# ProPrj_RS485_to_TTL_Converter_2026-02-25.net
KiCad netlist of a schematic drawn in EasyEDA Pro
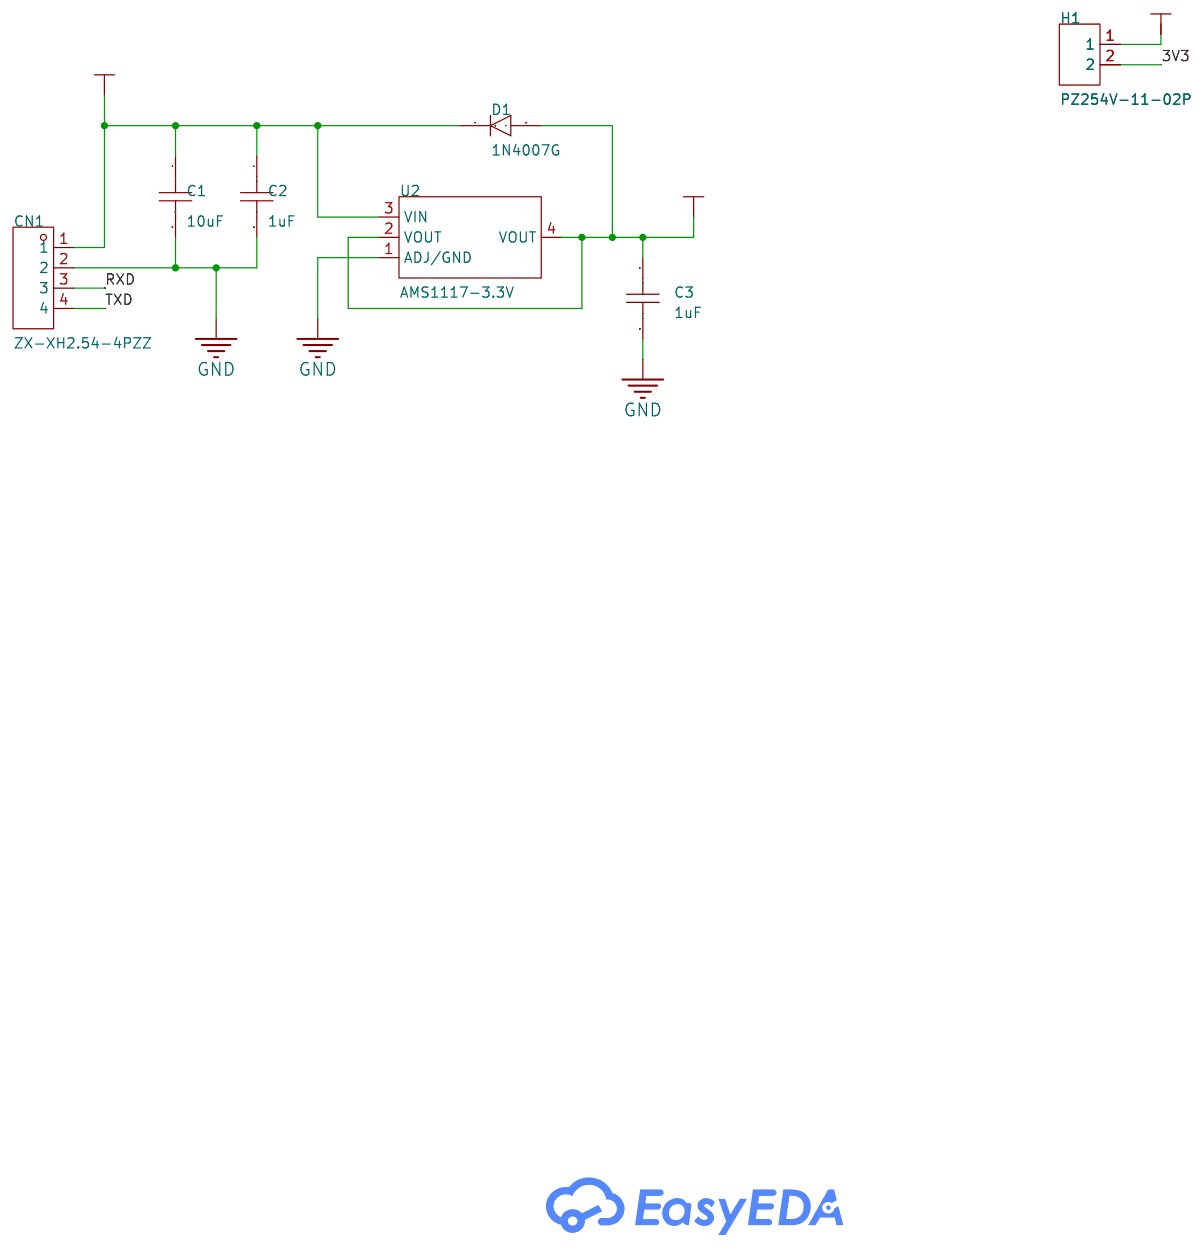
[diagram p0: Power Supply]
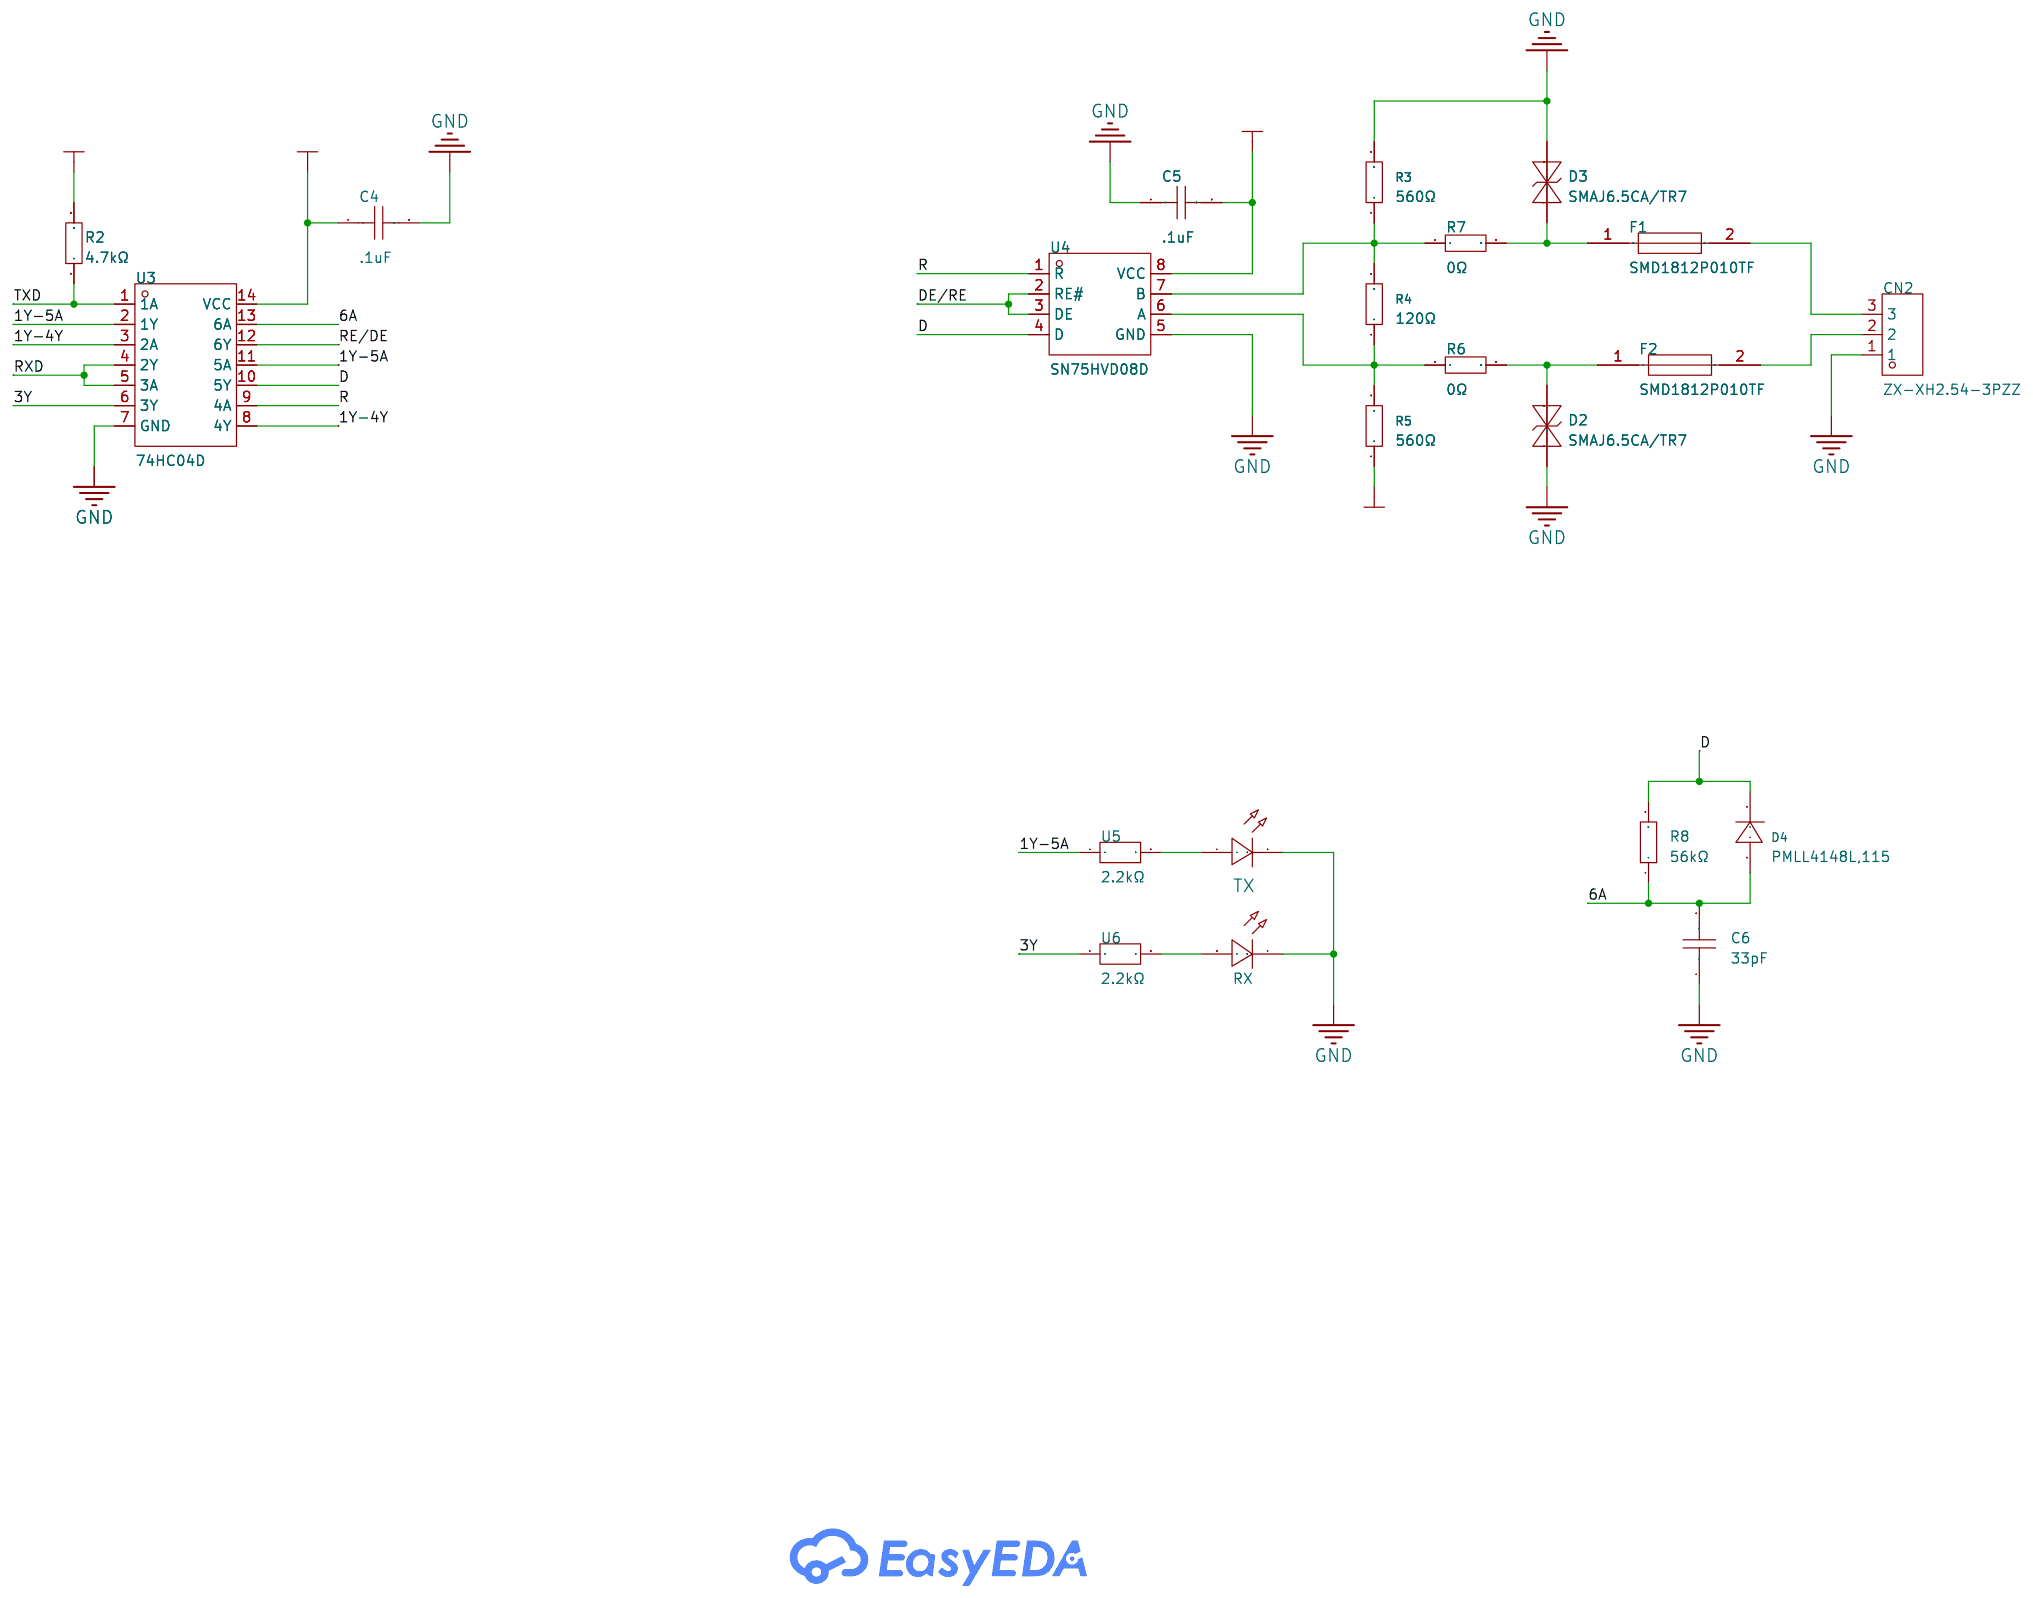
[diagram p1: RS485]

(export (version "E")
  (design (tool "Eeschema 10.0.6"))
  (components
    (comp (ref "C1")
      (value "10uF")
      (footprint "easyedapro:C0603")
      (libsource (lib "easyedapro") (part "CAP"))
    )
    (comp (ref "C2") (value "1uF") (footprint "easyedapro:C0603") (libsource (lib "easyedapro") (part "CAP")))
    (comp (ref "C3") (value "1uF") (footprint "easyedapro:C0603") (libsource (lib "easyedapro") (part "CAP")))
    (comp (ref "CN1")
      (value "ZX-XH2.54-4PZZ")
      (footprint "easyedapro:CONN-TH_4P-P2.50_4PIN")
      (fields (field (name "Manufacturer") "Megastar(兆星)"))
      (libsource (lib "easyedapro") (part "ZX-XH2.54-4PZZ"))
    )
    (comp (ref "D1")
      (value "1N4007G")
      (footprint "easyedapro:SMA_L4.4-W2.6-LS5.0-RD")
      (fields (field (name "Manufacturer") "SHIKUES(时科)"))
      (libsource (lib "easyedapro") (part "1N4007G"))
    )
    (comp (ref "H1")
      (value "PZ254V-11-02P")
      (footprint "easyedapro:HDR-TH_2P-P2.54-V-M")
      (fields (field (name "Manufacturer") "XFCN(兴飞)"))
      (libsource (lib "easyedapro") (part "PZ254V-11-02P"))
    )
    (comp (ref "U2")
      (value "AMS1117-3.3V")
      (footprint "easyedapro:SOT-223-4_L6.5-W3.5-P2.30-LS7.0-BR")
      (fields (field (name "Manufacturer") "WPMtek(维攀)"))
      (libsource (lib "easyedapro") (part "AMS1117-3.3V"))
    )
    (comp (ref "C4")
      (value ".1uF")
      (footprint "easyedapro:C0603")
      (libsource (lib "easyedapro") (part "CAP"))
    )
    (comp (ref "C5")
      (value ".1uF")
      (footprint "easyedapro:C0603")
      (libsource (lib "easyedapro") (part "CAP"))
    )
    (comp (ref "C6")
      (value "33pF")
      (footprint "easyedapro:C0603")
      (libsource (lib "easyedapro") (part "CAP"))
    )
    (comp (ref "CN2")
      (value "ZX-XH2.54-3PZZ")
      (footprint "easyedapro:CONN-TH_3P-P2.54_2501S-3P")
      (fields (field (name "Manufacturer") "Megastar(兆星)"))
      (libsource (lib "easyedapro") (part "ZX-XH2.54-3PZZ"))
    )
    (comp (ref "D2")
      (value "SMAJ6.5CA/TR7")
      (footprint "easyedapro:SMA_L4.3-W2.6-LS5.1-BI")
      (fields (field (name "Manufacturer") "Brightking(君耀电子)"))
      (libsource (lib "easyedapro") (part "SMAJ6.5CA/TR7"))
    )
    (comp (ref "D3")
      (value "SMAJ6.5CA/TR7")
      (footprint "easyedapro:SMA_L4.3-W2.6-LS5.1-BI")
      (fields (field (name "Manufacturer") "Brightking(君耀电子)"))
      (libsource (lib "easyedapro") (part "SMAJ6.5CA/TR7"))
    )
    (comp (ref "D4")
      (value "PMLL4148L,115")
      (footprint "easyedapro:SOD-80_L3.5-W1.5-RD")
      (fields (field (name "Manufacturer") "Nexperia(安世)"))
      (libsource (lib "easyedapro") (part "PMLL4148L,115"))
    )
    (comp (ref "F1")
      (value "SMD1812P010TF")
      (footprint "easyedapro:F1812")
      (fields (field (name "Manufacturer") "PTTC(聚鼎)"))
      (libsource (lib "easyedapro") (part "SMD1812P010TF_C495355"))
    )
    (comp (ref "F2")
      (value "SMD1812P010TF")
      (footprint "easyedapro:F1812")
      (fields (field (name "Manufacturer") "PTTC(聚鼎)"))
      (libsource (lib "easyedapro") (part "SMD1812P010TF_C495355"))
    )
    (comp (ref "R2")
      (value "4.7kΩ")
      (footprint "easyedapro:R0805")
      (fields
        (field (name "Manufacturer Part") "0805W8F4701T5E")
        (field (name "Manufacturer") "UNI-ROYAL(厚声)")
      )
      (libsource (lib "easyedapro") (part "0805W8F4701T5E"))
    )
    (comp (ref "R3")
      (value "560Ω")
      (footprint "easyedapro:R0805")
      (fields
        (field (name "Manufacturer Part") "0805W8F5600T5E")
        (field (name "Manufacturer") "UNI-ROYAL(厚声)")
      )
      (libsource (lib "easyedapro") (part "0805W8F5600T5E"))
    )
    (comp (ref "R4")
      (value "120Ω")
      (footprint "easyedapro:R0805")
      (fields
        (field (name "Manufacturer Part") "0805W8F1200T5E")
        (field (name "Manufacturer") "UNI-ROYAL(厚声)")
      )
      (libsource (lib "easyedapro") (part "0805W8F1200T5E"))
    )
    (comp (ref "R5")
      (value "560Ω")
      (footprint "easyedapro:R0805")
      (fields
        (field (name "Manufacturer Part") "0805W8F5600T5E")
        (field (name "Manufacturer") "UNI-ROYAL(厚声)")
      )
      (libsource (lib "easyedapro") (part "0805W8F5600T5E"))
    )
    (comp (ref "R6")
      (value "0Ω")
      (footprint "easyedapro:R0805")
      (fields
        (field (name "Manufacturer Part") "0805W8F0000T5E")
        (field (name "Manufacturer") "UNI-ROYAL(厚声)")
      )
      (libsource (lib "easyedapro") (part "0805W8F0000T5E"))
    )
    (comp (ref "R7")
      (value "0Ω")
      (footprint "easyedapro:R0805")
      (fields
        (field (name "Manufacturer Part") "0805W8F0000T5E")
        (field (name "Manufacturer") "UNI-ROYAL(厚声)")
      )
      (libsource (lib "easyedapro") (part "0805W8F0000T5E"))
    )
    (comp (ref "R8")
      (value "56kΩ")
      (footprint "easyedapro:R0805")
      (fields
        (field (name "Manufacturer Part") "0805W8F5602T5E")
        (field (name "Manufacturer") "UNI-ROYAL(厚声)")
      )
      (libsource (lib "easyedapro") (part "0805W8F5602T5E"))
    )
    (comp (ref "RX")
      (value "~")
      (footprint "easyedapro:LED0603-RD_GREEN")
      (libsource (lib "easyedapro") (part "LED_G"))
    )
    (comp (ref "TX")
      (value "~")
      (footprint "easyedapro:LED0603-R-RD")
      (libsource (lib "easyedapro") (part "LED_R"))
    )
    (comp (ref "U3")
      (value "74HC04D")
      (footprint "easyedapro:SOP-14_L8.6-W3.9-P1.27-LS6.0-BL")
      (fields (field (name "Manufacturer") "HTC"))
      (libsource (lib "easyedapro") (part "74HC04D"))
    )
    (comp (ref "U4")
      (value "SN75HVD08D")
      (footprint "easyedapro:SOIC-8_L4.9-W3.9-P1.27-LS6.0-BL")
      (fields (field (name "Manufacturer") "TI(德州仪器)"))
      (libsource (lib "easyedapro") (part "SN75HVD08D"))
    )
    (comp (ref "U5")
      (value "2.2kΩ")
      (footprint "easyedapro:R0805")
      (fields (field (name "Manufacturer Part") "FRC0805J222 TS") (field (name "Manufacturer") "FOJAN(富捷)"))
      (libsource (lib "easyedapro") (part "FRC0805J222 TS"))
    )
    (comp (ref "U6")
      (value "2.2kΩ")
      (footprint "easyedapro:R0805")
      (fields (field (name "Manufacturer Part") "FRC0805J222 TS") (field (name "Manufacturer") "FOJAN(富捷)"))
      (libsource (lib "easyedapro") (part "FRC0805J222 TS"))
    )
  )
  (nets
    (net (code "1") (name "1Y-4Y") (class "Default")
      (node (ref "U3") (pin "3") (pinfunction "2A_3") (pintype "unspecified"))
      (node (ref "U3") (pin "8") (pinfunction "4Y_8") (pintype "unspecified"))
    )
    (net (code "2") (name "1Y-5A") (class "Default")
      (node (ref "U3") (pin "11") (pinfunction "5A_11") (pintype "unspecified"))
      (node (ref "U3") (pin "2") (pinfunction "1Y_2") (pintype "unspecified"))
      (node (ref "U5") (pin "1") (pinfunction "1_1") (pintype "unspecified"))
    )
    (net (code "3") (name "3V3") (class "Default")
      (node (ref "C3") (pin "1") (pinfunction "1_1") (pintype "input"))
      (node (ref "C4") (pin "1") (pinfunction "1_1") (pintype "input"))
      (node (ref "C5") (pin "2") (pinfunction "2_2") (pintype "input"))
      (node (ref "D1") (pin "2") (pinfunction "A_2") (pintype "unspecified"))
      (node (ref "H1") (pin "2") (pinfunction "2_2") (pintype "unspecified"))
      (node (ref "R2") (pin "2") (pinfunction "2_2") (pintype "input"))
      (node (ref "R5") (pin "1") (pinfunction "1_1") (pintype "input"))
      (node (ref "U2") (pin "2") (pinfunction "VOUT_2") (pintype "unspecified"))
      (node (ref "U2") (pin "4") (pinfunction "VOUT_4") (pintype "unspecified"))
      (node (ref "U3") (pin "14") (pinfunction "VCC_14") (pintype "unspecified"))
      (node (ref "U4") (pin "8") (pinfunction "VCC_8") (pintype "unspecified"))
    )
    (net (code "4") (name "3Y") (class "Default")
      (node (ref "U3") (pin "6") (pinfunction "3Y_6") (pintype "unspecified"))
      (node (ref "U6") (pin "1") (pinfunction "1_1") (pintype "unspecified"))
    )
    (net (code "5") (name "5V") (class "Default")
      (node (ref "C1") (pin "1") (pinfunction "1_1") (pintype "input"))
      (node (ref "C2") (pin "1") (pinfunction "1_1") (pintype "input"))
      (node (ref "CN1") (pin "1") (pinfunction "1_1") (pintype "unspecified"))
      (node (ref "D1") (pin "1") (pinfunction "C_1") (pintype "unspecified"))
      (node (ref "H1") (pin "1") (pinfunction "1_1") (pintype "unspecified"))
      (node (ref "U2") (pin "3") (pinfunction "VIN_3") (pintype "unspecified"))
    )
    (net (code "6") (name "6A") (class "Default")
      (node (ref "C6") (pin "2") (pinfunction "2_2") (pintype "input"))
      (node (ref "D4") (pin "2") (pinfunction "A_2") (pintype "input"))
      (node (ref "R8") (pin "1") (pinfunction "1_1") (pintype "input"))
      (node (ref "U3") (pin "13") (pinfunction "6A_13") (pintype "unspecified"))
    )
    (net (code "7") (name "D") (class "Default")
      (node (ref "D4") (pin "1") (pinfunction "K_1") (pintype "input"))
      (node (ref "R8") (pin "2") (pinfunction "2_2") (pintype "input"))
      (node (ref "U3") (pin "10") (pinfunction "5Y_10") (pintype "unspecified"))
      (node (ref "U4") (pin "4") (pinfunction "D_4") (pintype "unspecified"))
    )
    (net (code "8") (name "DE{slash}RE") (class "Default")
      (node (ref "U4") (pin "2") (pinfunction "RE#_2") (pintype "unspecified"))
      (node (ref "U4") (pin "3") (pinfunction "DE_3") (pintype "unspecified"))
    )
    (net (code "9") (name "GND") (class "Default")
      (node (ref "C1") (pin "2") (pinfunction "2_2") (pintype "input"))
      (node (ref "C2") (pin "2") (pinfunction "2_2") (pintype "input"))
      (node (ref "C3") (pin "2") (pinfunction "2_2") (pintype "input"))
      (node (ref "C4") (pin "2") (pinfunction "2_2") (pintype "input"))
      (node (ref "C5") (pin "1") (pinfunction "1_1") (pintype "input"))
      (node (ref "C6") (pin "1") (pinfunction "1_1") (pintype "input"))
      (node (ref "CN1") (pin "2") (pinfunction "2_2") (pintype "unspecified"))
      (node (ref "CN2") (pin "1") (pinfunction "1_1") (pintype "unspecified"))
      (node (ref "D2") (pin "1") (pinfunction "1_1") (pintype "unspecified"))
      (node (ref "D3") (pin "2") (pinfunction "2_2") (pintype "unspecified"))
      (node (ref "R3") (pin "2") (pinfunction "2_2") (pintype "input"))
      (node (ref "RX") (pin "1") (pinfunction "C_1") (pintype "input"))
      (node (ref "TX") (pin "2") (pinfunction "C_2") (pintype "input"))
      (node (ref "U2") (pin "1") (pinfunction "ADJ/GND_1") (pintype "unspecified"))
      (node (ref "U3") (pin "7") (pinfunction "GND_7") (pintype "unspecified"))
      (node (ref "U4") (pin "5") (pinfunction "GND_5") (pintype "unspecified"))
    )
    (net (code "10") (name "Net-(CN2-Pad2)") (class "Default")
      (node (ref "CN2") (pin "2") (pinfunction "2_2") (pintype "unspecified"))
      (node (ref "F2") (pin "2") (pinfunction "2_2") (pintype "unspecified"))
    )
    (net (code "11") (name "Net-(CN2-Pad3)") (class "Default")
      (node (ref "CN2") (pin "3") (pinfunction "3_3") (pintype "unspecified"))
      (node (ref "F1") (pin "2") (pinfunction "2_2") (pintype "unspecified"))
    )
    (net (code "12") (name "Net-(D2-Pad2)") (class "Default")
      (node (ref "D2") (pin "2") (pinfunction "2_2") (pintype "unspecified"))
      (node (ref "F2") (pin "1") (pinfunction "1_1") (pintype "unspecified"))
      (node (ref "R6") (pin "2") (pinfunction "2_2") (pintype "input"))
    )
    (net (code "13") (name "Net-(D3-Pad1)") (class "Default")
      (node (ref "D3") (pin "1") (pinfunction "1_1") (pintype "unspecified"))
      (node (ref "F1") (pin "1") (pinfunction "1_1") (pintype "unspecified"))
      (node (ref "R7") (pin "2") (pinfunction "2_2") (pintype "input"))
    )
    (net (code "14") (name "Net-(RX-A)") (class "Default")
      (node (ref "RX") (pin "2") (pinfunction "A_2") (pintype "input"))
      (node (ref "U6") (pin "2") (pinfunction "2_2") (pintype "unspecified"))
    )
    (net (code "15") (name "Net-(TX-A)") (class "Default")
      (node (ref "TX") (pin "1") (pinfunction "A_1") (pintype "input"))
      (node (ref "U5") (pin "2") (pinfunction "2_2") (pintype "unspecified"))
    )
    (net (code "16") (name "Net-(U4-A)") (class "Default")
      (node (ref "R4") (pin "1") (pinfunction "1_1") (pintype "input"))
      (node (ref "R5") (pin "2") (pinfunction "2_2") (pintype "input"))
      (node (ref "R6") (pin "1") (pinfunction "1_1") (pintype "input"))
      (node (ref "U4") (pin "6") (pinfunction "A_6") (pintype "unspecified"))
    )
    (net (code "17") (name "Net-(U4-B)") (class "Default")
      (node (ref "R3") (pin "1") (pinfunction "1_1") (pintype "input"))
      (node (ref "R4") (pin "2") (pinfunction "2_2") (pintype "input"))
      (node (ref "R7") (pin "1") (pinfunction "1_1") (pintype "input"))
      (node (ref "U4") (pin "7") (pinfunction "B_7") (pintype "unspecified"))
    )
    (net (code "18") (name "R") (class "Default")
      (node (ref "U3") (pin "9") (pinfunction "4A_9") (pintype "unspecified"))
      (node (ref "U4") (pin "1") (pinfunction "R_1") (pintype "unspecified"))
    )
    (net (code "19") (name "RE{slash}DE") (class "Default")
      (node (ref "U3") (pin "12") (pinfunction "6Y_12") (pintype "unspecified"))
    )
    (net (code "20") (name "RXD") (class "Default")
      (node (ref "CN1") (pin "3") (pinfunction "3_3") (pintype "unspecified"))
      (node (ref "U3") (pin "4") (pinfunction "2Y_4") (pintype "unspecified"))
      (node (ref "U3") (pin "5") (pinfunction "3A_5") (pintype "unspecified"))
    )
    (net (code "21") (name "TXD") (class "Default")
      (node (ref "CN1") (pin "4") (pinfunction "4_4") (pintype "unspecified"))
      (node (ref "R2") (pin "1") (pinfunction "1_1") (pintype "input"))
      (node (ref "U3") (pin "1") (pinfunction "1A_1") (pintype "unspecified"))
    )
  )
)
